# US_EPS_BIC.net
KiCad netlist of a schematic drawn in Altium Designer
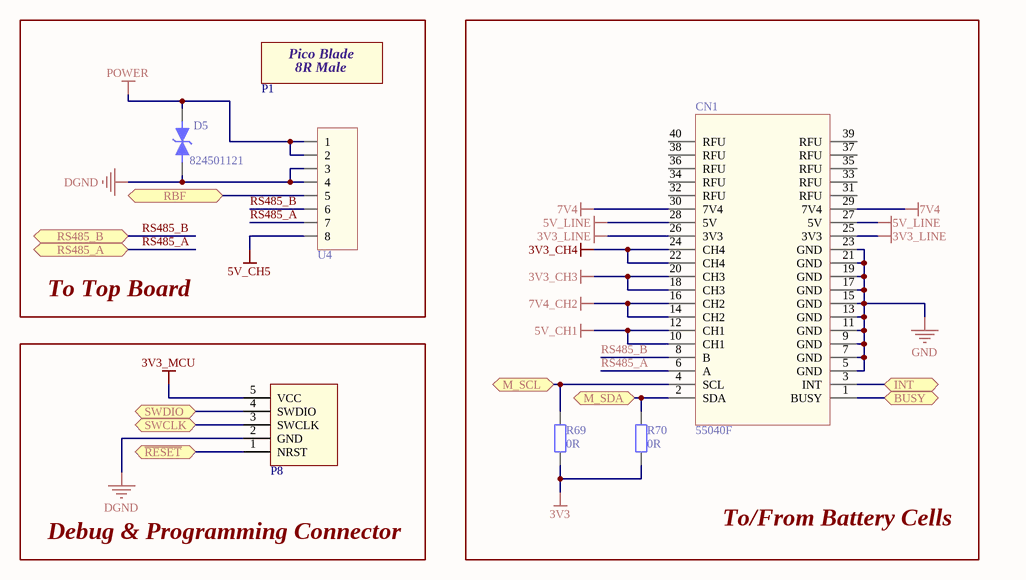
[diagram p0: US_EPS_BIC.SchDoc]

(export (version "E")
  (design (tool "Eeschema 10.0.6"))
  (components
    (comp (ref "CN1")
      (value "55040F")
      (footprint "HEADER_40PIN_12MM2")
      (description "CONN HEADER R/A 40POS 2.54MM")
      (fields (field (name "MANUFACTURER") "On Shore Technology Inc."))
      (libsource (lib "alfasat_lib") (part "ALFASAT_BIC"))
    )
    (comp (ref "D5")
      (value "824501121")
      (footprint "alfasat_lib_eps:DIOM4227X25N")
      (description "TVS DIODE 12V 19.9V DO214AC")
      (fields (field (name "MANUFACTURER") "Wurth Electronics Inc."))
      (libsource (lib "alfasat_lib_eps") (part "824501121_TVS"))
    )
    (comp (ref "P1")
      (value "PicoBlade_8R_MALE")
      (description "MALE Connector Header Surface Mount, Right Angle 8 position 0.049\" (1.25mm)")
      (fields (field (name "MANUFACTURER") "China"))
      (libsource (lib "alfasat_lib_eps") (part "PicoBlade_8R_M"))
    )
    (comp (ref "P8")
      (value "SWD")
      (footprint "SWD_CON_VAR1")
      (description "SWDIO SWCLK VDD GND NRST")
      (libsource (lib "alfasat_parts_lib") (part "SWD-CONNECTOR_VAR1"))
    )
    (comp (ref "R69")
      (value "0R")
      (footprint "R0603_IPC_MD")
      (description "RES SMD 0 OHM JUMPER 1/10W 0603")
      (fields
        (field (name "MANUFACTURER") "Bourns Inc.")
        (field (name "MANUFACTURER PART NUMBER") "CR0603-J/-000ELF")
      )
      (libsource (lib "alfasat_lib") (part "CR0603-J/-000ELF"))
    )
    (comp (ref "R70")
      (value "0R")
      (footprint "R0603_IPC_MD")
      (description "RES SMD 0 OHM JUMPER 1/10W 0603")
      (fields
        (field (name "MANUFACTURER") "Bourns Inc.")
        (field (name "MANUFACTURER PART NUMBER") "CR0603-J/-000ELF")
      )
      (libsource (lib "alfasat_lib") (part "CR0603-J/-000ELF"))
    )
    (comp (ref "U4")
      (value "PicoBlade_8R")
      (footprint "PB_53398-0871_RIGHT")
      (description "Connector Header Surface Mount, Right Angle 8 position 0.049\" (1.25mm)")
      (fields (field (name "MANUFACTURER") "China"))
      (libsource (lib "alfasat_parts_lib") (part "PicoBlade_8R"))
    )
  )
  (nets
    (net (code "1") (name "/BUSY") (class "Default")
      (node (ref "CN1") (pin "1") (pinfunction "BUSY_1") (pintype "passive"))
    )
    (net (code "2") (name "/INT") (class "Default")
      (node (ref "CN1") (pin "3") (pinfunction "INT_3") (pintype "passive"))
    )
    (net (code "3") (name "/M_SCL") (class "Default")
      (node (ref "CN1") (pin "4") (pinfunction "SCL_4") (pintype "passive"))
      (node (ref "R69") (pin "2") (pinfunction "2_2") (pintype "passive"))
    )
    (net (code "4") (name "/M_SDA") (class "Default")
      (node (ref "CN1") (pin "2") (pinfunction "SDA_2") (pintype "passive"))
      (node (ref "R70") (pin "2") (pinfunction "2_2") (pintype "passive"))
    )
    (net (code "5") (name "/RBF") (class "Default")
      (node (ref "U4") (pin "5") (pinfunction "5_5") (pintype "passive"))
    )
    (net (code "6") (name "/RS485_A") (class "Default")
      (node (ref "CN1") (pin "6") (pinfunction "A_6") (pintype "passive"))
      (node (ref "U4") (pin "7") (pinfunction "7_7") (pintype "passive"))
    )
    (net (code "7") (name "/RS485_B") (class "Default")
      (node (ref "CN1") (pin "8") (pinfunction "B_8") (pintype "passive"))
      (node (ref "U4") (pin "6") (pinfunction "6_6") (pintype "passive"))
    )
    (net (code "8") (name "/SWCLK") (class "Default")
      (node (ref "P8") (pin "3") (pinfunction "SWCLK_3") (pintype "passive"))
    )
    (net (code "9") (name "/SWDIO") (class "Default")
      (node (ref "P8") (pin "4") (pinfunction "SWDIO_4") (pintype "passive"))
    )
    (net (code "10") (name "/~{RESET}") (class "Default")
      (node (ref "P8") (pin "1") (pinfunction "NRST_1") (pintype "passive"))
    )
    (net (code "11") (name "3V3") (class "Default")
      (node (ref "R69") (pin "1") (pinfunction "1_1") (pintype "passive"))
      (node (ref "R70") (pin "1") (pinfunction "1_1") (pintype "passive"))
    )
    (net (code "12") (name "3V3_CH3") (class "Default")
      (node (ref "CN1") (pin "18") (pinfunction "CH3_18") (pintype "passive"))
      (node (ref "CN1") (pin "20") (pinfunction "CH3_20") (pintype "passive"))
    )
    (net (code "13") (name "3V3_CH4") (class "Default")
      (node (ref "CN1") (pin "22") (pinfunction "CH4_22") (pintype "passive"))
      (node (ref "CN1") (pin "24") (pinfunction "CH4_24") (pintype "passive"))
    )
    (net (code "14") (name "3V3_LINE") (class "Default")
      (node (ref "CN1") (pin "25") (pinfunction "3V3_25") (pintype "passive"))
      (node (ref "CN1") (pin "26") (pinfunction "3V3_26") (pintype "passive"))
    )
    (net (code "15") (name "3V3_MCU") (class "Default")
      (node (ref "P8") (pin "5") (pinfunction "VCC_5") (pintype "passive"))
    )
    (net (code "16") (name "5V_CH1") (class "Default")
      (node (ref "CN1") (pin "10") (pinfunction "CH1_10") (pintype "passive"))
      (node (ref "CN1") (pin "12") (pinfunction "CH1_12") (pintype "passive"))
    )
    (net (code "17") (name "5V_CH5") (class "Default")
      (node (ref "U4") (pin "8") (pinfunction "8_8") (pintype "passive"))
    )
    (net (code "18") (name "5V_LINE") (class "Default")
      (node (ref "CN1") (pin "27") (pinfunction "5V_27") (pintype "passive"))
      (node (ref "CN1") (pin "28") (pinfunction "5V_28") (pintype "passive"))
    )
    (net (code "19") (name "7V4") (class "Default")
      (node (ref "CN1") (pin "29") (pinfunction "7V4_29") (pintype "passive"))
      (node (ref "CN1") (pin "30") (pinfunction "7V4_30") (pintype "passive"))
    )
    (net (code "20") (name "7V4_CH2") (class "Default")
      (node (ref "CN1") (pin "14") (pinfunction "CH2_14") (pintype "passive"))
      (node (ref "CN1") (pin "16") (pinfunction "CH2_16") (pintype "passive"))
    )
    (net (code "21") (name "DGND") (class "Default")
      (node (ref "D5") (pin "1") (pinfunction "1_1") (pintype "passive"))
      (node (ref "P8") (pin "2") (pinfunction "GND_2") (pintype "passive"))
      (node (ref "U4") (pin "3") (pinfunction "3_3") (pintype "passive"))
      (node (ref "U4") (pin "4") (pinfunction "4_4") (pintype "passive"))
    )
    (net (code "22") (name "GND") (class "Default")
      (node (ref "CN1") (pin "11") (pinfunction "GND_11") (pintype "passive"))
      (node (ref "CN1") (pin "13") (pinfunction "GND_13") (pintype "passive"))
      (node (ref "CN1") (pin "15") (pinfunction "GND_15") (pintype "passive"))
      (node (ref "CN1") (pin "17") (pinfunction "GND_17") (pintype "passive"))
      (node (ref "CN1") (pin "19") (pinfunction "GND_19") (pintype "passive"))
      (node (ref "CN1") (pin "21") (pinfunction "GND_21") (pintype "passive"))
      (node (ref "CN1") (pin "23") (pinfunction "GND_23") (pintype "passive"))
      (node (ref "CN1") (pin "5") (pinfunction "GND_5") (pintype "passive"))
      (node (ref "CN1") (pin "7") (pinfunction "GND_7") (pintype "passive"))
      (node (ref "CN1") (pin "9") (pinfunction "GND_9") (pintype "passive"))
    )
    (net (code "23") (name "POWER") (class "Default")
      (node (ref "D5") (pin "2") (pinfunction "2_2") (pintype "passive"))
      (node (ref "U4") (pin "1") (pinfunction "1_1") (pintype "passive"))
      (node (ref "U4") (pin "2") (pinfunction "2_2") (pintype "passive"))
    )
    (net (code "24") (name "unconnected-(CN1-RFU-Pad31)") (class "Default")
      (node (ref "CN1") (pin "31") (pinfunction "RFU_31") (pintype "passive"))
    )
    (net (code "25") (name "unconnected-(CN1-RFU-Pad32)") (class "Default")
      (node (ref "CN1") (pin "32") (pinfunction "RFU_32") (pintype "passive"))
    )
    (net (code "26") (name "unconnected-(CN1-RFU-Pad33)") (class "Default")
      (node (ref "CN1") (pin "33") (pinfunction "RFU_33") (pintype "passive"))
    )
    (net (code "27") (name "unconnected-(CN1-RFU-Pad34)") (class "Default")
      (node (ref "CN1") (pin "34") (pinfunction "RFU_34") (pintype "passive"))
    )
    (net (code "28") (name "unconnected-(CN1-RFU-Pad35)") (class "Default")
      (node (ref "CN1") (pin "35") (pinfunction "RFU_35") (pintype "passive"))
    )
    (net (code "29") (name "unconnected-(CN1-RFU-Pad36)") (class "Default")
      (node (ref "CN1") (pin "36") (pinfunction "RFU_36") (pintype "passive"))
    )
    (net (code "30") (name "unconnected-(CN1-RFU-Pad37)") (class "Default")
      (node (ref "CN1") (pin "37") (pinfunction "RFU_37") (pintype "passive"))
    )
    (net (code "31") (name "unconnected-(CN1-RFU-Pad38)") (class "Default")
      (node (ref "CN1") (pin "38") (pinfunction "RFU_38") (pintype "passive"))
    )
    (net (code "32") (name "unconnected-(CN1-RFU-Pad39)") (class "Default")
      (node (ref "CN1") (pin "39") (pinfunction "RFU_39") (pintype "passive"))
    )
    (net (code "33") (name "unconnected-(CN1-RFU-Pad40)") (class "Default")
      (node (ref "CN1") (pin "40") (pinfunction "RFU_40") (pintype "passive"))
    )
  )
)
